# Pi_Tracker3.net
KiCad netlist of a schematic drawn in EAGLE
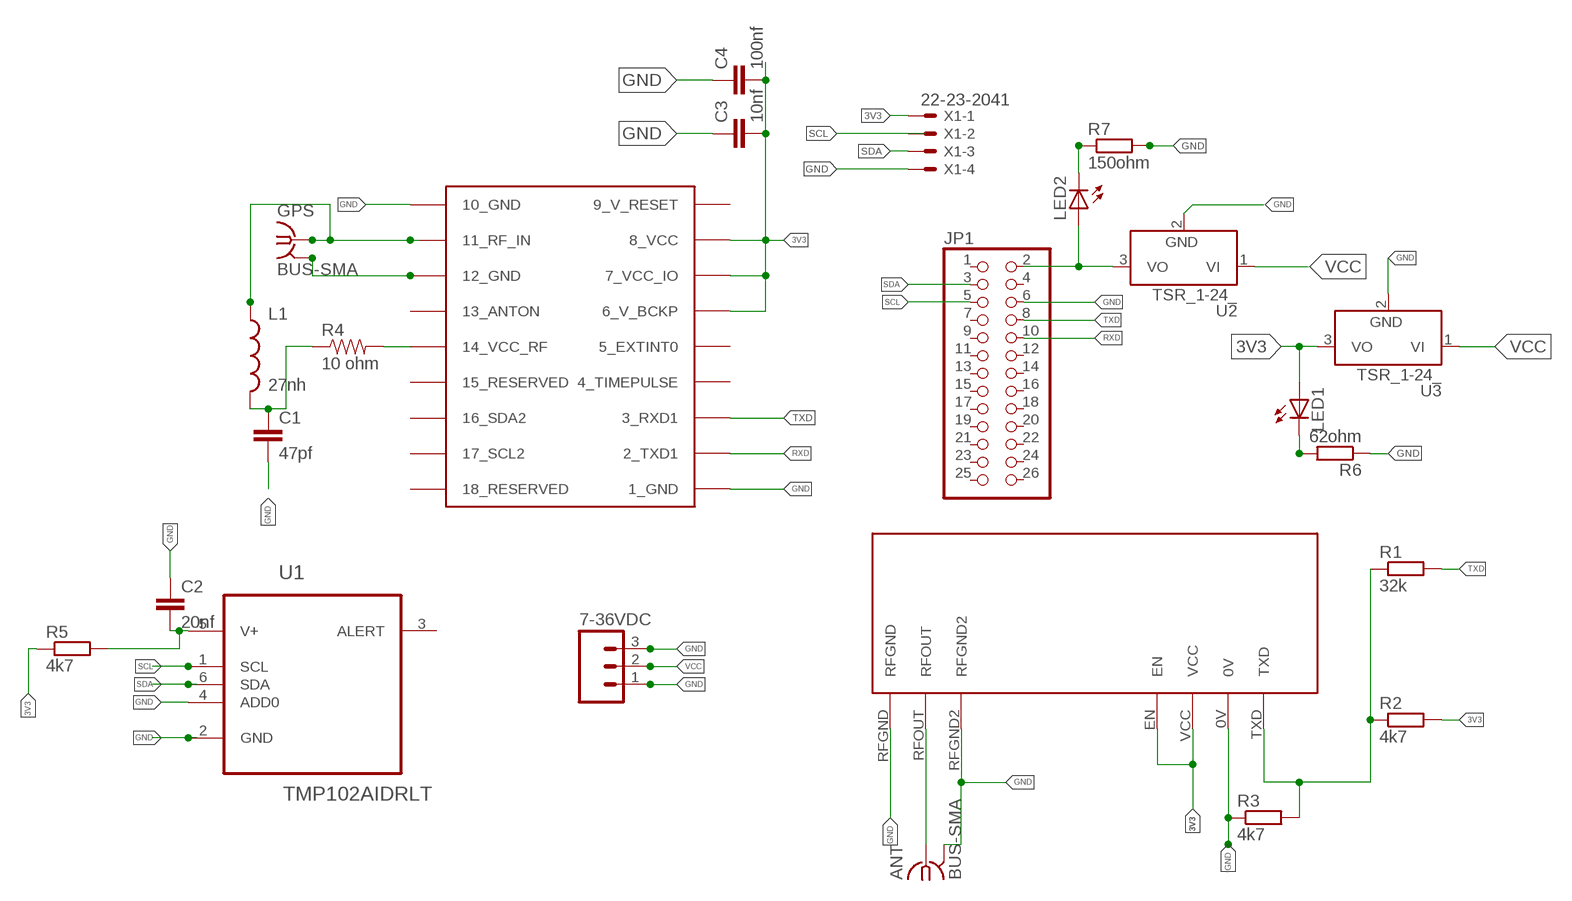
[diagram p0: schematic, sheet 1]

(export (version "E")
  (design (tool "Eeschema 10.0.6"))
  (components
    (comp (ref "7-36VDC")
      (value "M03PTH")
      (footprint "eagle-import:1X03")
      (libsource (lib "eagle-import") (part "M03PTH"))
    )
    (comp (ref "ANT")
      (value "BUS-SMA")
      (footprint "eagle-import:BUS-SMA")
      (libsource (lib "eagle-import") (part "BUS-SMA"))
    )
    (comp (ref "C1")
      (value "47pf")
      (footprint "eagle-import:0603-CAP")
      (libsource (lib "eagle-import") (part "CAP0603-CAP"))
    )
    (comp (ref "C2")
      (value "20nf")
      (footprint "eagle-import:C0603")
      (libsource (lib "eagle-import") (part "C-EUC0603"))
    )
    (comp (ref "C3")
      (value "10nf")
      (footprint "eagle-import:C0603")
      (libsource (lib "eagle-import") (part "C-EUC0603"))
    )
    (comp (ref "C4")
      (value "100nf")
      (footprint "eagle-import:C0603")
      (libsource (lib "eagle-import") (part "C-EUC0603"))
    )
    (comp (ref "GPS")
      (value "BUS-SMA")
      (footprint "eagle-import:BUS-SMA")
      (libsource (lib "eagle-import") (part "BUS-SMA"))
    )
    (comp (ref "JP1")
      (value "PINHD-2X13")
      (footprint "eagle-import:2X13")
      (libsource (lib "eagle-import") (part "PINHD-2X13"))
    )
    (comp (ref "L1")
      (value "27nh")
      (footprint "eagle-import:0603")
      (libsource (lib "eagle-import") (part "INDUCTOR0603"))
    )
    (comp (ref "LED1")
      (value "LEDSML0603")
      (footprint "eagle-import:SML0603")
      (libsource (lib "eagle-import") (part "LEDSML0603"))
    )
    (comp (ref "LED2")
      (value "LEDSML0603")
      (footprint "eagle-import:SML0603")
      (libsource (lib "eagle-import") (part "LEDSML0603"))
    )
    (comp (ref "R1")
      (value "32k")
      (footprint "eagle-import:R0603")
      (libsource (lib "eagle-import") (part "R-EU_R0603"))
    )
    (comp (ref "R2")
      (value "4k7")
      (footprint "eagle-import:R0603")
      (libsource (lib "eagle-import") (part "R-EU_R0603"))
    )
    (comp (ref "R3")
      (value "4k7")
      (footprint "eagle-import:R0603")
      (libsource (lib "eagle-import") (part "R-EU_R0603"))
    )
    (comp (ref "R4")
      (value "10 ohm")
      (footprint "eagle-import:0603-RES")
      (libsource (lib "eagle-import") (part "RESISTOR0603"))
    )
    (comp (ref "R5")
      (value "4k7")
      (footprint "eagle-import:R0603")
      (libsource (lib "eagle-import") (part "R-EU_R0603"))
    )
    (comp (ref "R6")
      (value "62ohm")
      (footprint "eagle-import:R0603")
      (libsource (lib "eagle-import") (part "R-EU_R0603"))
    )
    (comp (ref "R7")
      (value "150ohm")
      (footprint "eagle-import:R0603")
      (libsource (lib "eagle-import") (part "R-EU_R0603"))
    )
    (comp (ref "U$1")
      (value "NTX2")
      (footprint "eagle-import:NTX2")
      (libsource (lib "eagle-import") (part "NTX2"))
    )
    (comp (ref "U$2")
      (value "UBLOX_MAX")
      (footprint "eagle-import:UBLOX_MAX")
      (libsource (lib "eagle-import") (part "UBLOX_MAX"))
    )
    (comp (ref "U1")
      (value "TMP102AIDRLT")
      (footprint "eagle-import:SOT50P160X60-6N")
      (libsource (lib "eagle-import") (part "TMP102AIDRLT"))
    )
    (comp (ref "U2")
      (value "TSR_1-24_")
      (footprint "eagle-import:TSR-1")
      (libsource (lib "eagle-import") (part "TSR_1-24_"))
    )
    (comp (ref "U3")
      (value "TSR_1-24_")
      (footprint "eagle-import:TSR-1")
      (libsource (lib "eagle-import") (part "TSR_1-24_"))
    )
    (comp (ref "X1")
      (value "22-23-2041")
      (footprint "eagle-import:22-23-2041")
      (fields (field (name "MF") "MOLEX"))
      (libsource (lib "eagle-import") (part "22-23-2041"))
    )
  )
  (nets
    (net (code "1") (name "/9_V_RESET") (class "Default")
      (node (ref "U$2") (pin "9_V_RESET") (pinfunction "9_V_RESET_9_V_RESET") (pintype "power_in"))
    )
    (net (code "2") (name "3V3") (class "Default")
      (node (ref "C2") (pin "2") (pinfunction "2_2") (pintype "passive"))
      (node (ref "C3") (pin "2") (pinfunction "2_2") (pintype "passive"))
      (node (ref "C4") (pin "2") (pinfunction "2_2") (pintype "passive"))
      (node (ref "LED1") (pin "A") (pinfunction "A_A") (pintype "passive"))
      (node (ref "R2") (pin "2") (pinfunction "2_2") (pintype "passive"))
      (node (ref "R5") (pin "1") (pinfunction "1_1") (pintype "passive"))
      (node (ref "R5") (pin "2") (pinfunction "2_2") (pintype "passive"))
      (node (ref "U$1") (pin "EN") (pinfunction "EN_EN") (pintype "bidirectional"))
      (node (ref "U$1") (pin "VCC") (pinfunction "VCC_VCC") (pintype "bidirectional"))
      (node (ref "U$2") (pin "6_V_BCKP") (pinfunction "6_V_BCKP_6_V_BCKP") (pintype "bidirectional"))
      (node (ref "U$2") (pin "7_VCC_IO") (pinfunction "7_VCC_IO_7_VCC_IO") (pintype "power_in"))
      (node (ref "U$2") (pin "8_VCC") (pinfunction "8_VCC_8_VCC") (pintype "power_in"))
      (node (ref "U1") (pin "5") (pinfunction "V+_5") (pintype "power_in"))
      (node (ref "U3") (pin "3") (pinfunction "VO_3") (pintype "power_in"))
      (node (ref "X1") (pin "1") (pinfunction "S_1") (pintype "passive"))
    )
    (net (code "3") (name "GND") (class "Default")
      (node (ref "7-36VDC") (pin "1") (pinfunction "1_1") (pintype "passive"))
      (node (ref "7-36VDC") (pin "3") (pinfunction "3_3") (pintype "passive"))
      (node (ref "ANT") (pin "2") (pinfunction "GND_2") (pintype "power_in"))
      (node (ref "ANT") (pin "3") (pinfunction "GND_3") (pintype "power_in"))
      (node (ref "ANT") (pin "4") (pinfunction "GND_4") (pintype "power_in"))
      (node (ref "ANT") (pin "5") (pinfunction "GND_5") (pintype "power_in"))
      (node (ref "C1") (pin "2") (pinfunction "2_2") (pintype "passive"))
      (node (ref "C2") (pin "1") (pinfunction "1_1") (pintype "passive"))
      (node (ref "C3") (pin "1") (pinfunction "1_1") (pintype "passive"))
      (node (ref "C4") (pin "1") (pinfunction "1_1") (pintype "passive"))
      (node (ref "GPS") (pin "2") (pinfunction "GND_2") (pintype "power_in"))
      (node (ref "GPS") (pin "3") (pinfunction "GND_3") (pintype "power_in"))
      (node (ref "GPS") (pin "4") (pinfunction "GND_4") (pintype "power_in"))
      (node (ref "GPS") (pin "5") (pinfunction "GND_5") (pintype "power_in"))
      (node (ref "JP1") (pin "6") (pinfunction "6_6") (pintype "passive"))
      (node (ref "R3") (pin "1") (pinfunction "1_1") (pintype "passive"))
      (node (ref "R6") (pin "1") (pinfunction "1_1") (pintype "passive"))
      (node (ref "R7") (pin "2") (pinfunction "2_2") (pintype "passive"))
      (node (ref "U$1") (pin "0V") (pinfunction "0V_0V") (pintype "bidirectional"))
      (node (ref "U$1") (pin "RFGND") (pinfunction "RFGND_RFGND") (pintype "bidirectional"))
      (node (ref "U$1") (pin "RFGND2") (pinfunction "RFGND2_RFGND2") (pintype "bidirectional"))
      (node (ref "U$2") (pin "10_GND") (pinfunction "10_GND_10_GND") (pintype "power_in"))
      (node (ref "U$2") (pin "12_GND") (pinfunction "12_GND_12_GND") (pintype "power_in"))
      (node (ref "U$2") (pin "1_GND") (pinfunction "1_GND_1_GND") (pintype "power_in"))
      (node (ref "U1") (pin "2") (pinfunction "GND_2") (pintype "passive"))
      (node (ref "U1") (pin "4") (pinfunction "ADD0_4") (pintype "input"))
      (node (ref "U2") (pin "2") (pinfunction "GND_2") (pintype "power_in"))
      (node (ref "U3") (pin "2") (pinfunction "GND_2") (pintype "power_in"))
      (node (ref "X1") (pin "4") (pinfunction "S_4") (pintype "passive"))
    )
    (net (code "4") (name "Net-(ANT-Pad1)") (class "Default")
      (node (ref "ANT") (pin "1") (pinfunction "1_1") (pintype "passive"))
      (node (ref "U$1") (pin "RFOUT") (pinfunction "RFOUT_RFOUT") (pintype "bidirectional"))
    )
    (net (code "5") (name "Net-(C1-Pad1)") (class "Default")
      (node (ref "C1") (pin "1") (pinfunction "1_1") (pintype "passive"))
      (node (ref "L1") (pin "2") (pinfunction "2_2") (pintype "passive"))
      (node (ref "R4") (pin "1") (pinfunction "1_1") (pintype "passive"))
    )
    (net (code "6") (name "Net-(GPS-Pad1)") (class "Default")
      (node (ref "GPS") (pin "1") (pinfunction "1_1") (pintype "passive"))
      (node (ref "L1") (pin "1") (pinfunction "1_1") (pintype "passive"))
      (node (ref "U$2") (pin "11_RF_IN") (pinfunction "11_RF_IN_11_RF_IN") (pintype "bidirectional"))
    )
    (net (code "7") (name "Net-(LED1-PadC)") (class "Default")
      (node (ref "LED1") (pin "C") (pinfunction "C_C") (pintype "passive"))
      (node (ref "R6") (pin "2") (pinfunction "2_2") (pintype "passive"))
    )
    (net (code "8") (name "Net-(LED2-PadC)") (class "Default")
      (node (ref "LED2") (pin "C") (pinfunction "C_C") (pintype "passive"))
      (node (ref "R7") (pin "1") (pinfunction "1_1") (pintype "passive"))
    )
    (net (code "9") (name "Net-(R1-Pad1)") (class "Default")
      (node (ref "R1") (pin "1") (pinfunction "1_1") (pintype "passive"))
      (node (ref "R2") (pin "1") (pinfunction "1_1") (pintype "passive"))
      (node (ref "R3") (pin "2") (pinfunction "2_2") (pintype "passive"))
      (node (ref "U$1") (pin "TXD") (pinfunction "TXD_TXD") (pintype "bidirectional"))
    )
    (net (code "10") (name "Net-(R4-Pad2)") (class "Default")
      (node (ref "R4") (pin "2") (pinfunction "2_2") (pintype "passive"))
      (node (ref "U$2") (pin "14_VCC_RF") (pinfunction "14_VCC_RF_14_VCC_RF") (pintype "bidirectional"))
    )
    (net (code "11") (name "Net-(U2-VO)") (class "Default")
      (node (ref "JP1") (pin "2") (pinfunction "2_2") (pintype "passive"))
      (node (ref "LED2") (pin "A") (pinfunction "A_A") (pintype "passive"))
      (node (ref "U2") (pin "3") (pinfunction "VO_3") (pintype "power_in"))
    )
    (net (code "12") (name "RXD") (class "Default")
      (node (ref "JP1") (pin "10") (pinfunction "10_10") (pintype "passive"))
      (node (ref "U$2") (pin "2_TXD1") (pinfunction "2_TXD1_2_TXD1") (pintype "bidirectional"))
    )
    (net (code "13") (name "SCL") (class "Default")
      (node (ref "JP1") (pin "5") (pinfunction "5_5") (pintype "passive"))
      (node (ref "U1") (pin "1") (pinfunction "SCL_1") (pintype "bidirectional"))
      (node (ref "X1") (pin "2") (pinfunction "S_2") (pintype "passive"))
    )
    (net (code "14") (name "SDA") (class "Default")
      (node (ref "JP1") (pin "3") (pinfunction "3_3") (pintype "passive"))
      (node (ref "U1") (pin "6") (pinfunction "SDA_6") (pintype "bidirectional"))
      (node (ref "X1") (pin "3") (pinfunction "S_3") (pintype "passive"))
    )
    (net (code "15") (name "TXD") (class "Default")
      (node (ref "JP1") (pin "8") (pinfunction "8_8") (pintype "passive"))
      (node (ref "R1") (pin "2") (pinfunction "2_2") (pintype "passive"))
      (node (ref "U$2") (pin "3_RXD1") (pinfunction "3_RXD1_3_RXD1") (pintype "bidirectional"))
    )
    (net (code "16") (name "VCC") (class "Default")
      (node (ref "7-36VDC") (pin "2") (pinfunction "2_2") (pintype "passive"))
      (node (ref "U2") (pin "1") (pinfunction "VI_1") (pintype "power_in"))
      (node (ref "U3") (pin "1") (pinfunction "VI_1") (pintype "power_in"))
    )
    (net (code "17") (name "unconnected-(JP1-Pad1)") (class "Default")
      (node (ref "JP1") (pin "1") (pinfunction "1_1") (pintype "passive"))
    )
    (net (code "18") (name "unconnected-(JP1-Pad4)") (class "Default")
      (node (ref "JP1") (pin "4") (pinfunction "4_4") (pintype "passive"))
    )
    (net (code "19") (name "unconnected-(JP1-Pad7)") (class "Default")
      (node (ref "JP1") (pin "7") (pinfunction "7_7") (pintype "passive"))
    )
    (net (code "20") (name "unconnected-(JP1-Pad9)") (class "Default")
      (node (ref "JP1") (pin "9") (pinfunction "9_9") (pintype "passive"))
    )
    (net (code "21") (name "unconnected-(JP1-Pad11)") (class "Default")
      (node (ref "JP1") (pin "11") (pinfunction "11_11") (pintype "passive"))
    )
    (net (code "22") (name "unconnected-(JP1-Pad12)") (class "Default")
      (node (ref "JP1") (pin "12") (pinfunction "12_12") (pintype "passive"))
    )
    (net (code "23") (name "unconnected-(JP1-Pad13)") (class "Default")
      (node (ref "JP1") (pin "13") (pinfunction "13_13") (pintype "passive"))
    )
    (net (code "24") (name "unconnected-(JP1-Pad14)") (class "Default")
      (node (ref "JP1") (pin "14") (pinfunction "14_14") (pintype "passive"))
    )
    (net (code "25") (name "unconnected-(JP1-Pad15)") (class "Default")
      (node (ref "JP1") (pin "15") (pinfunction "15_15") (pintype "passive"))
    )
    (net (code "26") (name "unconnected-(JP1-Pad16)") (class "Default")
      (node (ref "JP1") (pin "16") (pinfunction "16_16") (pintype "passive"))
    )
    (net (code "27") (name "unconnected-(JP1-Pad17)") (class "Default")
      (node (ref "JP1") (pin "17") (pinfunction "17_17") (pintype "passive"))
    )
    (net (code "28") (name "unconnected-(JP1-Pad18)") (class "Default")
      (node (ref "JP1") (pin "18") (pinfunction "18_18") (pintype "passive"))
    )
    (net (code "29") (name "unconnected-(JP1-Pad19)") (class "Default")
      (node (ref "JP1") (pin "19") (pinfunction "19_19") (pintype "passive"))
    )
    (net (code "30") (name "unconnected-(JP1-Pad20)") (class "Default")
      (node (ref "JP1") (pin "20") (pinfunction "20_20") (pintype "passive"))
    )
    (net (code "31") (name "unconnected-(JP1-Pad21)") (class "Default")
      (node (ref "JP1") (pin "21") (pinfunction "21_21") (pintype "passive"))
    )
    (net (code "32") (name "unconnected-(JP1-Pad22)") (class "Default")
      (node (ref "JP1") (pin "22") (pinfunction "22_22") (pintype "passive"))
    )
    (net (code "33") (name "unconnected-(JP1-Pad23)") (class "Default")
      (node (ref "JP1") (pin "23") (pinfunction "23_23") (pintype "passive"))
    )
    (net (code "34") (name "unconnected-(JP1-Pad24)") (class "Default")
      (node (ref "JP1") (pin "24") (pinfunction "24_24") (pintype "passive"))
    )
    (net (code "35") (name "unconnected-(JP1-Pad25)") (class "Default")
      (node (ref "JP1") (pin "25") (pinfunction "25_25") (pintype "passive"))
    )
    (net (code "36") (name "unconnected-(JP1-Pad26)") (class "Default")
      (node (ref "JP1") (pin "26") (pinfunction "26_26") (pintype "passive"))
    )
    (net (code "37") (name "unconnected-(U$2-Pad4_TIMEPULSE)") (class "Default")
      (node (ref "U$2") (pin "4_TIMEPULSE") (pinfunction "4_TIMEPULSE_4_TIMEPULSE") (pintype "bidirectional"))
    )
    (net (code "38") (name "unconnected-(U$2-Pad5_EXTINT0)") (class "Default")
      (node (ref "U$2") (pin "5_EXTINT0") (pinfunction "5_EXTINT0_5_EXTINT0") (pintype "bidirectional"))
    )
    (net (code "39") (name "unconnected-(U$2-Pad13_ANTON)") (class "Default")
      (node (ref "U$2") (pin "13_ANTON") (pinfunction "13_ANTON_13_ANTON") (pintype "bidirectional"))
    )
    (net (code "40") (name "unconnected-(U$2-Pad15_RESERVED)") (class "Default")
      (node (ref "U$2") (pin "15_RESERVED") (pinfunction "15_RESERVED_15_RESERVED") (pintype "bidirectional"))
    )
    (net (code "41") (name "unconnected-(U$2-Pad16_SDA2)") (class "Default")
      (node (ref "U$2") (pin "16_SDA2") (pinfunction "16_SDA2_16_SDA2") (pintype "bidirectional"))
    )
    (net (code "42") (name "unconnected-(U$2-Pad17_SCL2)") (class "Default")
      (node (ref "U$2") (pin "17_SCL2") (pinfunction "17_SCL2_17_SCL2") (pintype "bidirectional"))
    )
    (net (code "43") (name "unconnected-(U$2-Pad18_RESERVED)") (class "Default")
      (node (ref "U$2") (pin "18_RESERVED") (pinfunction "18_RESERVED_18_RESERVED") (pintype "bidirectional"))
    )
    (net (code "44") (name "unconnected-(U1-ALERT-Pad3)") (class "Default")
      (node (ref "U1") (pin "3") (pinfunction "ALERT_3") (pintype "output"))
    )
  )
)
